# sduino.net
KiCad netlist of a schematic drawn in EAGLE
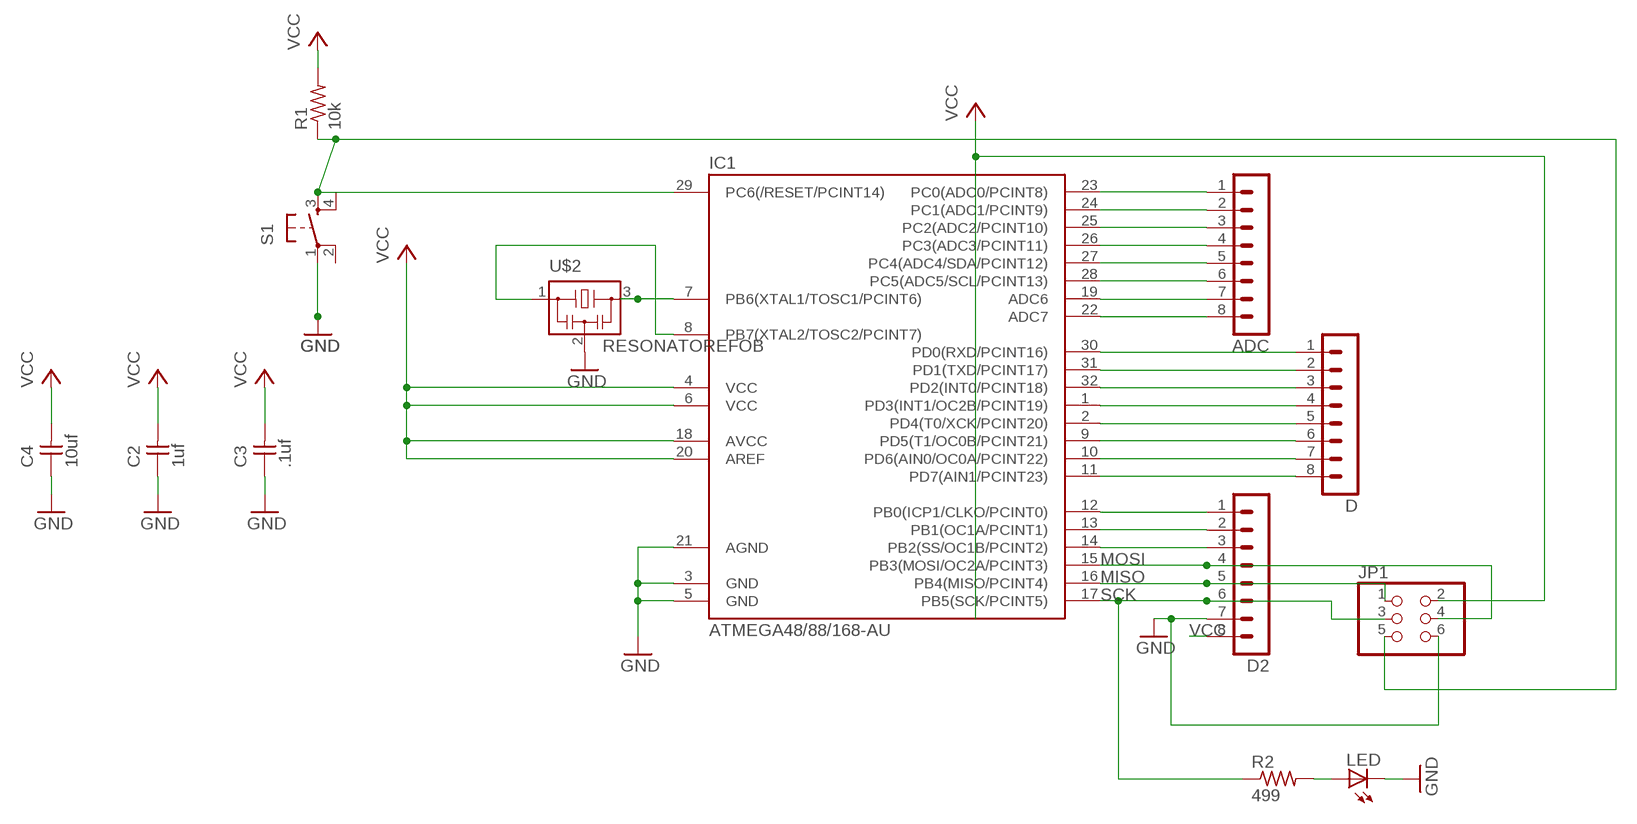
[diagram p0: schematic, sheet 1]

(export (version "E")
  (design (tool "Eeschema 10.0.6"))
  (components
    (comp (ref "ADC")
      (value "MA08-1")
      (footprint "eagle-import:MA08-1")
      (libsource (lib "eagle-import") (part "MA08-1"))
    )
    (comp (ref "C2")
      (value "1uf")
      (footprint "eagle-import:1206")
      (libsource (lib "eagle-import") (part "UNPOLARIZED_CAPACITOR1206"))
    )
    (comp (ref "C3")
      (value ".1uf")
      (footprint "eagle-import:1206")
      (libsource (lib "eagle-import") (part "UNPOLARIZED_CAPACITOR1206"))
    )
    (comp (ref "C4")
      (value "10uf")
      (footprint "eagle-import:1206")
      (libsource (lib "eagle-import") (part "UNPOLARIZED_CAPACITOR1206"))
    )
    (comp (ref "D")
      (value "MA08-1")
      (footprint "eagle-import:MA08-1")
      (libsource (lib "eagle-import") (part "MA08-1"))
    )
    (comp (ref "D2")
      (value "MA08-1")
      (footprint "eagle-import:MA08-1")
      (libsource (lib "eagle-import") (part "MA08-1"))
    )
    (comp (ref "IC1")
      (value "ATMEGA48/88/168-AU")
      (footprint "eagle-import:TQFP32-08")
      (libsource (lib "eagle-import") (part "ATMEGA48/88/168-AU"))
    )
    (comp (ref "JP1")
      (value "PINHD-2X3")
      (footprint "eagle-import:2X03")
      (libsource (lib "eagle-import") (part "PINHD-2X3"))
    )
    (comp (ref "LED")
      (value "LED1206")
      (footprint "eagle-import:1206")
      (libsource (lib "eagle-import") (part "LED1206"))
    )
    (comp (ref "R1")
      (value "10k")
      (footprint "eagle-import:1206")
      (libsource (lib "eagle-import") (part "RESISTOR1206"))
    )
    (comp (ref "R2")
      (value "499")
      (footprint "eagle-import:1206")
      (libsource (lib "eagle-import") (part "RESISTOR1206"))
    )
    (comp (ref "S1")
      (value "6MM_SWITCH6MM_SWITCH")
      (footprint "eagle-import:6MM_SWITCH")
      (libsource (lib "eagle-import") (part "6MM_SWITCH6MM_SWITCH"))
    )
    (comp (ref "U$2")
      (value "RESONATOREFOB")
      (footprint "eagle-import:EFOBM")
      (libsource (lib "eagle-import") (part "RESONATOREFOB"))
    )
  )
  (nets
    (net (code "1") (name "/MISO") (class "Default")
      (node (ref "D2") (pin "5") (pinfunction "5_5") (pintype "passive"))
      (node (ref "IC1") (pin "16") (pinfunction "PB4(MISO/PCINT4)_16") (pintype "bidirectional"))
      (node (ref "JP1") (pin "1") (pinfunction "1_1") (pintype "passive"))
    )
    (net (code "2") (name "/MOSI") (class "Default")
      (node (ref "D2") (pin "4") (pinfunction "4_4") (pintype "passive"))
      (node (ref "IC1") (pin "15") (pinfunction "PB3(MOSI/OC2A/PCINT3)_15") (pintype "bidirectional"))
      (node (ref "JP1") (pin "4") (pinfunction "4_4") (pintype "passive"))
    )
    (net (code "3") (name "/SCK") (class "Default")
      (node (ref "D2") (pin "6") (pinfunction "6_6") (pintype "passive"))
      (node (ref "IC1") (pin "17") (pinfunction "PB5(SCK/PCINT5)_17") (pintype "bidirectional"))
      (node (ref "JP1") (pin "3") (pinfunction "3_3") (pintype "passive"))
      (node (ref "R2") (pin "1") (pinfunction "1_1") (pintype "passive"))
    )
    (net (code "4") (name "GND") (class "Default")
      (node (ref "C2") (pin "1") (pinfunction "1_1") (pintype "passive"))
      (node (ref "C3") (pin "1") (pinfunction "1_1") (pintype "passive"))
      (node (ref "C4") (pin "1") (pinfunction "1_1") (pintype "passive"))
      (node (ref "D2") (pin "7") (pinfunction "7_7") (pintype "passive"))
      (node (ref "IC1") (pin "21") (pinfunction "AGND_21") (pintype "power_in"))
      (node (ref "IC1") (pin "3") (pinfunction "GND_3") (pintype "power_in"))
      (node (ref "IC1") (pin "5") (pinfunction "GND_5") (pintype "power_in"))
      (node (ref "JP1") (pin "6") (pinfunction "6_6") (pintype "passive"))
      (node (ref "LED") (pin "2") (pinfunction "C_2") (pintype "passive"))
      (node (ref "S1") (pin "1") (pinfunction "P_1") (pintype "passive"))
      (node (ref "U$2") (pin "2") (pinfunction "2_2") (pintype "passive"))
    )
    (net (code "5") (name "Net-(IC1-ADC6)") (class "Default")
      (node (ref "ADC") (pin "7") (pinfunction "7_7") (pintype "passive"))
      (node (ref "IC1") (pin "19") (pinfunction "ADC6_19") (pintype "passive"))
    )
    (net (code "6") (name "Net-(IC1-ADC7)") (class "Default")
      (node (ref "ADC") (pin "8") (pinfunction "8_8") (pintype "passive"))
      (node (ref "IC1") (pin "22") (pinfunction "ADC7_22") (pintype "passive"))
    )
    (net (code "7") (name "Net-(IC1-PB0(ICP1{slash}CLKO{slash}PCINT0))") (class "Default")
      (node (ref "D2") (pin "1") (pinfunction "1_1") (pintype "passive"))
      (node (ref "IC1") (pin "12") (pinfunction "PB0(ICP1/CLKO/PCINT0)_12") (pintype "bidirectional"))
    )
    (net (code "8") (name "Net-(IC1-PB1(OC1A{slash}PCINT1))") (class "Default")
      (node (ref "D2") (pin "2") (pinfunction "2_2") (pintype "passive"))
      (node (ref "IC1") (pin "13") (pinfunction "PB1(OC1A/PCINT1)_13") (pintype "bidirectional"))
    )
    (net (code "9") (name "Net-(IC1-PB2(SS{slash}OC1B{slash}PCINT2))") (class "Default")
      (node (ref "D2") (pin "3") (pinfunction "3_3") (pintype "passive"))
      (node (ref "IC1") (pin "14") (pinfunction "PB2(SS/OC1B/PCINT2)_14") (pintype "bidirectional"))
    )
    (net (code "10") (name "Net-(IC1-PB6(XTAL1{slash}TOSC1{slash}PCINT6))") (class "Default")
      (node (ref "IC1") (pin "7") (pinfunction "PB6(XTAL1/TOSC1/PCINT6)_7") (pintype "bidirectional"))
      (node (ref "U$2") (pin "3") (pinfunction "3_3") (pintype "passive"))
    )
    (net (code "11") (name "Net-(IC1-PB7(XTAL2{slash}TOSC2{slash}PCINT7))") (class "Default")
      (node (ref "IC1") (pin "8") (pinfunction "PB7(XTAL2/TOSC2/PCINT7)_8") (pintype "bidirectional"))
      (node (ref "U$2") (pin "1") (pinfunction "1_1") (pintype "passive"))
    )
    (net (code "12") (name "Net-(IC1-PC0(ADC0{slash}PCINT8))") (class "Default")
      (node (ref "ADC") (pin "1") (pinfunction "1_1") (pintype "passive"))
      (node (ref "IC1") (pin "23") (pinfunction "PC0(ADC0/PCINT8)_23") (pintype "bidirectional"))
    )
    (net (code "13") (name "Net-(IC1-PC1(ADC1{slash}PCINT9))") (class "Default")
      (node (ref "ADC") (pin "2") (pinfunction "2_2") (pintype "passive"))
      (node (ref "IC1") (pin "24") (pinfunction "PC1(ADC1/PCINT9)_24") (pintype "bidirectional"))
    )
    (net (code "14") (name "Net-(IC1-PC2(ADC2{slash}PCINT10))") (class "Default")
      (node (ref "ADC") (pin "3") (pinfunction "3_3") (pintype "passive"))
      (node (ref "IC1") (pin "25") (pinfunction "PC2(ADC2/PCINT10)_25") (pintype "bidirectional"))
    )
    (net (code "15") (name "Net-(IC1-PC3(ADC3{slash}PCINT11))") (class "Default")
      (node (ref "ADC") (pin "4") (pinfunction "4_4") (pintype "passive"))
      (node (ref "IC1") (pin "26") (pinfunction "PC3(ADC3/PCINT11)_26") (pintype "bidirectional"))
    )
    (net (code "16") (name "Net-(IC1-PC4(ADC4{slash}SDA{slash}PCINT12))") (class "Default")
      (node (ref "ADC") (pin "5") (pinfunction "5_5") (pintype "passive"))
      (node (ref "IC1") (pin "27") (pinfunction "PC4(ADC4/SDA/PCINT12)_27") (pintype "bidirectional"))
    )
    (net (code "17") (name "Net-(IC1-PC5(ADC5{slash}SCL{slash}PCINT13))") (class "Default")
      (node (ref "ADC") (pin "6") (pinfunction "6_6") (pintype "passive"))
      (node (ref "IC1") (pin "28") (pinfunction "PC5(ADC5/SCL/PCINT13)_28") (pintype "bidirectional"))
    )
    (net (code "18") (name "Net-(IC1-PC6({slash}RESET{slash}PCINT14))") (class "Default")
      (node (ref "IC1") (pin "29") (pinfunction "PC6(/RESET/PCINT14)_29") (pintype "bidirectional"))
      (node (ref "JP1") (pin "5") (pinfunction "5_5") (pintype "passive"))
      (node (ref "R1") (pin "1") (pinfunction "1_1") (pintype "passive"))
      (node (ref "S1") (pin "3") (pinfunction "S_3") (pintype "passive"))
    )
    (net (code "19") (name "Net-(IC1-PD0(RXD{slash}PCINT16))") (class "Default")
      (node (ref "D") (pin "1") (pinfunction "1_1") (pintype "passive"))
      (node (ref "IC1") (pin "30") (pinfunction "PD0(RXD/PCINT16)_30") (pintype "bidirectional"))
    )
    (net (code "20") (name "Net-(IC1-PD1(TXD{slash}PCINT17))") (class "Default")
      (node (ref "D") (pin "2") (pinfunction "2_2") (pintype "passive"))
      (node (ref "IC1") (pin "31") (pinfunction "PD1(TXD/PCINT17)_31") (pintype "bidirectional"))
    )
    (net (code "21") (name "Net-(IC1-PD2(INT0{slash}PCINT18))") (class "Default")
      (node (ref "D") (pin "3") (pinfunction "3_3") (pintype "passive"))
      (node (ref "IC1") (pin "32") (pinfunction "PD2(INT0/PCINT18)_32") (pintype "bidirectional"))
    )
    (net (code "22") (name "Net-(IC1-PD3(INT1{slash}OC2B{slash}PCINT19))") (class "Default")
      (node (ref "D") (pin "4") (pinfunction "4_4") (pintype "passive"))
      (node (ref "IC1") (pin "1") (pinfunction "PD3(INT1/OC2B/PCINT19)_1") (pintype "bidirectional"))
    )
    (net (code "23") (name "Net-(IC1-PD4(T0{slash}XCK{slash}PCINT20))") (class "Default")
      (node (ref "D") (pin "5") (pinfunction "5_5") (pintype "passive"))
      (node (ref "IC1") (pin "2") (pinfunction "PD4(T0/XCK/PCINT20)_2") (pintype "bidirectional"))
    )
    (net (code "24") (name "Net-(IC1-PD5(T1{slash}OC0B{slash}PCINT21))") (class "Default")
      (node (ref "D") (pin "6") (pinfunction "6_6") (pintype "passive"))
      (node (ref "IC1") (pin "9") (pinfunction "PD5(T1/OC0B/PCINT21)_9") (pintype "bidirectional"))
    )
    (net (code "25") (name "Net-(IC1-PD6(AIN0{slash}OC0A{slash}PCINT22))") (class "Default")
      (node (ref "D") (pin "7") (pinfunction "7_7") (pintype "passive"))
      (node (ref "IC1") (pin "10") (pinfunction "PD6(AIN0/OC0A/PCINT22)_10") (pintype "bidirectional"))
    )
    (net (code "26") (name "Net-(IC1-PD7(AIN1{slash}PCINT23))") (class "Default")
      (node (ref "D") (pin "8") (pinfunction "8_8") (pintype "passive"))
      (node (ref "IC1") (pin "11") (pinfunction "PD7(AIN1/PCINT23)_11") (pintype "bidirectional"))
    )
    (net (code "27") (name "Net-(LED-A)") (class "Default")
      (node (ref "LED") (pin "1") (pinfunction "A_1") (pintype "passive"))
      (node (ref "R2") (pin "2") (pinfunction "2_2") (pintype "passive"))
    )
    (net (code "28") (name "VCC") (class "Default")
      (node (ref "C2") (pin "2") (pinfunction "2_2") (pintype "passive"))
      (node (ref "C3") (pin "2") (pinfunction "2_2") (pintype "passive"))
      (node (ref "C4") (pin "2") (pinfunction "2_2") (pintype "passive"))
      (node (ref "D2") (pin "8") (pinfunction "8_8") (pintype "passive"))
      (node (ref "IC1") (pin "18") (pinfunction "AVCC_18") (pintype "passive"))
      (node (ref "IC1") (pin "20") (pinfunction "AREF_20") (pintype "passive"))
      (node (ref "IC1") (pin "4") (pinfunction "VCC_4") (pintype "power_in"))
      (node (ref "IC1") (pin "6") (pinfunction "VCC_6") (pintype "power_in"))
      (node (ref "JP1") (pin "2") (pinfunction "2_2") (pintype "passive"))
      (node (ref "R1") (pin "2") (pinfunction "2_2") (pintype "passive"))
    )
    (net (code "29") (name "unconnected-(S1-P1-Pad2)") (class "Default")
      (node (ref "S1") (pin "2") (pinfunction "P1_2") (pintype "passive"))
    )
    (net (code "30") (name "unconnected-(S1-S1-Pad4)") (class "Default")
      (node (ref "S1") (pin "4") (pinfunction "S1_4") (pintype "passive"))
    )
  )
)
